# untitled.net
KiCad netlist of a schematic drawn in EAGLE
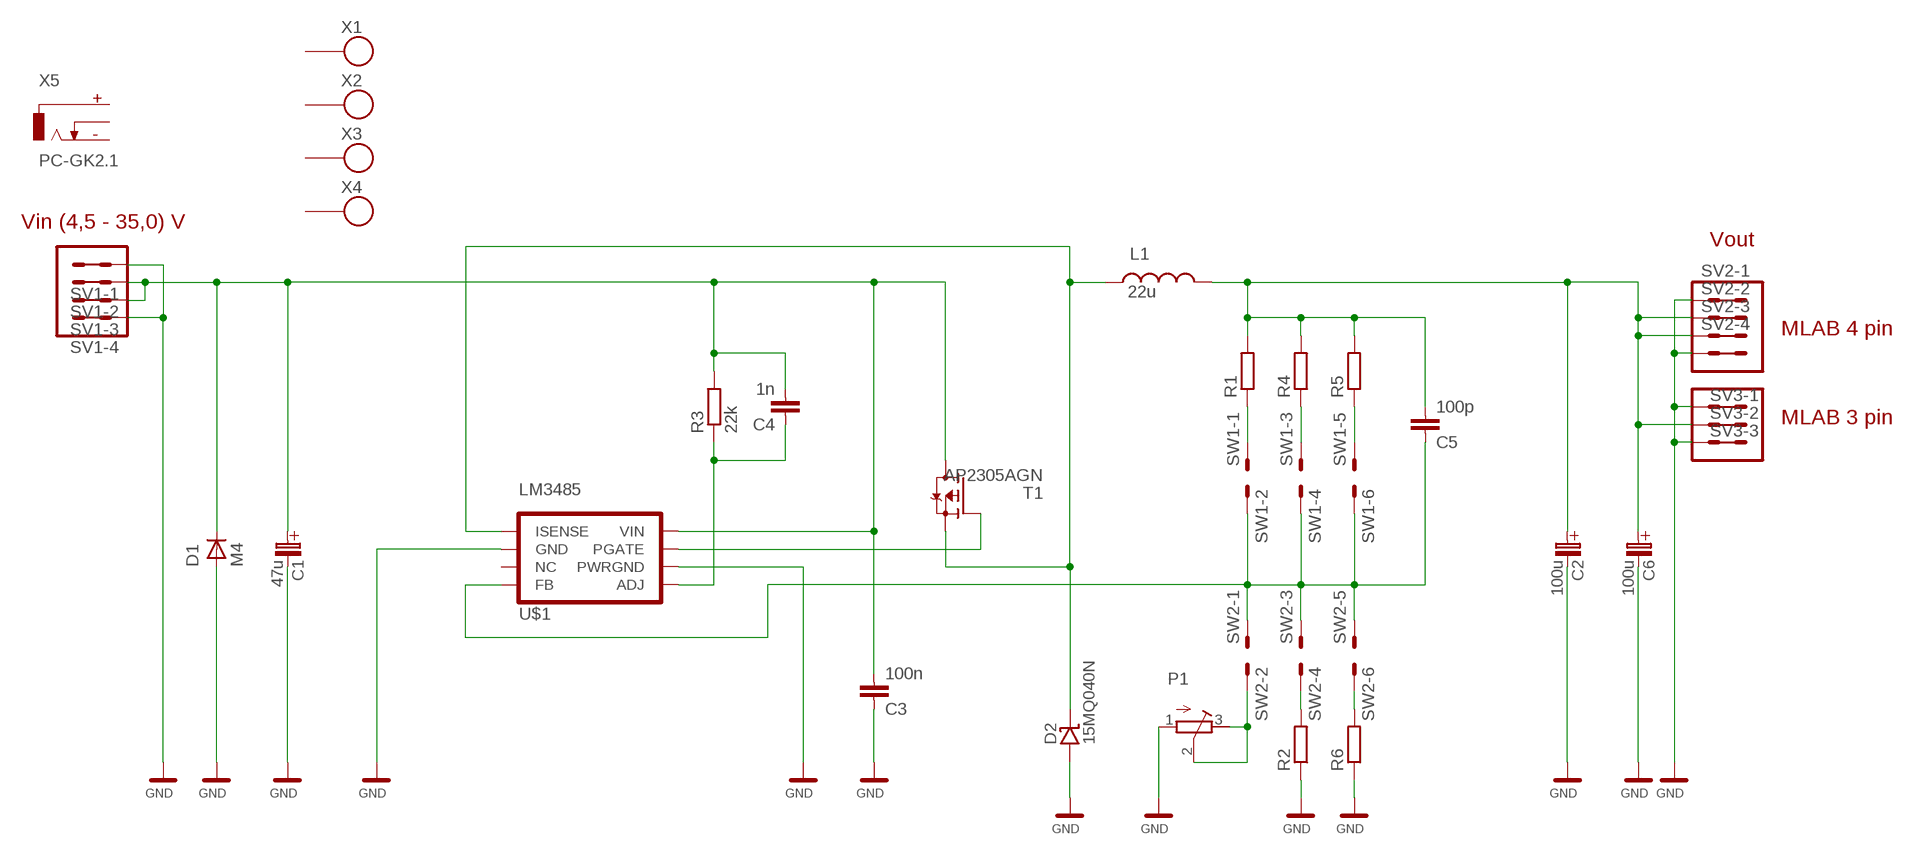
[diagram p0: schematic, sheet 1]

(export (version "E")
  (design (tool "Eeschema 10.0.6"))
  (components
    (comp (ref "C1") (value "47u") (footprint "eagle-import:C") (libsource (lib "eagle-import") (part "C")))
    (comp (ref "C2") (value "100u") (footprint "eagle-import:C") (libsource (lib "eagle-import") (part "C")))
    (comp (ref "C3")
      (value "100n")
      (footprint "eagle-import:C0805")
      (libsource (lib "eagle-import") (part "C0805"))
    )
    (comp (ref "C4")
      (value "1n")
      (footprint "eagle-import:C0805")
      (libsource (lib "eagle-import") (part "C0805"))
    )
    (comp (ref "C5")
      (value "100p")
      (footprint "eagle-import:C0805")
      (libsource (lib "eagle-import") (part "C0805"))
    )
    (comp (ref "C6") (value "100u") (footprint "eagle-import:C") (libsource (lib "eagle-import") (part "C")))
    (comp (ref "D1")
      (value "M4")
      (footprint "eagle-import:SMA")
      (libsource (lib "eagle-import") (part "D-OB.SMA"))
    )
    (comp (ref "D2")
      (value "15MQ040N")
      (footprint "eagle-import:SMA")
      (libsource (lib "eagle-import") (part "D-SHOTKY-SMA"))
    )
    (comp (ref "L1")
      (value "22u")
      (footprint "eagle-import:DE1205-10")
      (libsource (lib "eagle-import") (part "DE1205-10"))
    )
    (comp (ref "P1")
      (value "TRIMR_CA6XV")
      (footprint "eagle-import:TRIM_CA6XV")
      (libsource (lib "eagle-import") (part "TRIMR_CA6XV"))
    )
    (comp (ref "R1")
      (value "R0805")
      (footprint "eagle-import:0805")
      (libsource (lib "eagle-import") (part "R0805"))
    )
    (comp (ref "R2")
      (value "R0805")
      (footprint "eagle-import:0805")
      (libsource (lib "eagle-import") (part "R0805"))
    )
    (comp (ref "R3")
      (value "22k")
      (footprint "eagle-import:0805")
      (libsource (lib "eagle-import") (part "R0805"))
    )
    (comp (ref "R4")
      (value "R0805")
      (footprint "eagle-import:0805")
      (libsource (lib "eagle-import") (part "R0805"))
    )
    (comp (ref "R5")
      (value "R0805")
      (footprint "eagle-import:0805")
      (libsource (lib "eagle-import") (part "R0805"))
    )
    (comp (ref "R6")
      (value "R0805")
      (footprint "eagle-import:0805")
      (libsource (lib "eagle-import") (part "R0805"))
    )
    (comp (ref "SV1")
      (value "MA04-2")
      (footprint "eagle-import:MA04-2")
      (libsource (lib "eagle-import") (part "MA04-2"))
    )
    (comp (ref "SV2")
      (value "MA04-2")
      (footprint "eagle-import:MA04-2")
      (libsource (lib "eagle-import") (part "MA04-2"))
    )
    (comp (ref "SV3")
      (value "MA03-2")
      (footprint "eagle-import:MA03-2")
      (libsource (lib "eagle-import") (part "MA03-2"))
    )
    (comp (ref "SW1")
      (value "MA03-3")
      (footprint "eagle-import:MA03-2")
      (libsource (lib "eagle-import") (part "MA03-3"))
    )
    (comp (ref "SW2")
      (value "MA03-3")
      (footprint "eagle-import:MA03-2")
      (libsource (lib "eagle-import") (part "MA03-3"))
    )
    (comp (ref "T1")
      (value "AP2305AGN")
      (footprint "eagle-import:SOT23")
      (libsource (lib "eagle-import") (part "AP2305AGN"))
    )
    (comp (ref "U$1")
      (value "LM3485")
      (footprint "eagle-import:MSOP-8")
      (libsource (lib "eagle-import") (part "LM3485"))
    )
    (comp (ref "X1")
      (value "SROUB3M")
      (footprint "eagle-import:SROUB3M")
      (libsource (lib "eagle-import") (part "SROUB3M"))
    )
    (comp (ref "X2")
      (value "SROUB3M")
      (footprint "eagle-import:SROUB3M")
      (libsource (lib "eagle-import") (part "SROUB3M"))
    )
    (comp (ref "X3")
      (value "SROUB3M")
      (footprint "eagle-import:SROUB3M")
      (libsource (lib "eagle-import") (part "SROUB3M"))
    )
    (comp (ref "X4")
      (value "SROUB3M")
      (footprint "eagle-import:SROUB3M")
      (libsource (lib "eagle-import") (part "SROUB3M"))
    )
    (comp (ref "X5")
      (value "DC2.1MM")
      (footprint "eagle-import:DC2.1MM")
      (libsource (lib "eagle-import") (part "DC2.1MM"))
    )
  )
  (nets
    (net (code "1") (name "GND") (class "Default")
      (node (ref "C1") (pin "-") (pinfunction "C_EL-_-") (pintype "passive"))
      (node (ref "C2") (pin "-") (pinfunction "C_EL-_-") (pintype "passive"))
      (node (ref "C3") (pin "1") (pinfunction "1_1") (pintype "passive"))
      (node (ref "C6") (pin "-") (pinfunction "C_EL-_-") (pintype "passive"))
      (node (ref "D1") (pin "A") (pinfunction "A_A") (pintype "passive"))
      (node (ref "D2") (pin "A") (pinfunction "A_A") (pintype "passive"))
      (node (ref "P1") (pin "1") (pinfunction "1_1") (pintype "passive"))
      (node (ref "R2") (pin "1") (pinfunction "1_1") (pintype "passive"))
      (node (ref "R6") (pin "1") (pinfunction "1_1") (pintype "passive"))
      (node (ref "SV1") (pin "1") (pinfunction "K_1") (pintype "passive"))
      (node (ref "SV1") (pin "2") (pinfunction "K_2") (pintype "passive"))
      (node (ref "SV1") (pin "7") (pinfunction "K_7") (pintype "passive"))
      (node (ref "SV1") (pin "8") (pinfunction "K_8") (pintype "passive"))
      (node (ref "SV2") (pin "1") (pinfunction "K_1") (pintype "passive"))
      (node (ref "SV2") (pin "2") (pinfunction "K_2") (pintype "passive"))
      (node (ref "SV2") (pin "7") (pinfunction "K_7") (pintype "passive"))
      (node (ref "SV2") (pin "8") (pinfunction "K_8") (pintype "passive"))
      (node (ref "SV3") (pin "1") (pinfunction "K_1") (pintype "passive"))
      (node (ref "SV3") (pin "2") (pinfunction "K_2") (pintype "passive"))
      (node (ref "SV3") (pin "5") (pinfunction "K_5") (pintype "passive"))
      (node (ref "SV3") (pin "6") (pinfunction "K_6") (pintype "passive"))
      (node (ref "U$1") (pin "2") (pinfunction "GND_2") (pintype "passive"))
      (node (ref "U$1") (pin "6") (pinfunction "PWRGND_6") (pintype "passive"))
    )
    (net (code "2") (name "Net-(C1-C_EL+)") (class "Default")
      (node (ref "C1") (pin "+") (pinfunction "C_EL+_+") (pintype "passive"))
      (node (ref "C3") (pin "2") (pinfunction "2_2") (pintype "passive"))
      (node (ref "C4") (pin "2") (pinfunction "2_2") (pintype "passive"))
      (node (ref "D1") (pin "K") (pinfunction "C_K") (pintype "passive"))
      (node (ref "R3") (pin "2") (pinfunction "2_2") (pintype "passive"))
      (node (ref "SV1") (pin "3") (pinfunction "K_3") (pintype "passive"))
      (node (ref "SV1") (pin "4") (pinfunction "K_4") (pintype "passive"))
      (node (ref "SV1") (pin "5") (pinfunction "K_5") (pintype "passive"))
      (node (ref "SV1") (pin "6") (pinfunction "K_6") (pintype "passive"))
      (node (ref "T1") (pin "3") (pinfunction "D_3") (pintype "passive"))
      (node (ref "U$1") (pin "8") (pinfunction "VIN_8") (pintype "passive"))
    )
    (net (code "3") (name "Net-(C2-C_EL+)") (class "Default")
      (node (ref "C2") (pin "+") (pinfunction "C_EL+_+") (pintype "passive"))
      (node (ref "C5") (pin "2") (pinfunction "2_2") (pintype "passive"))
      (node (ref "C6") (pin "+") (pinfunction "C_EL+_+") (pintype "passive"))
      (node (ref "L1") (pin "P$2") (pinfunction "2_P$2") (pintype "passive"))
      (node (ref "R1") (pin "2") (pinfunction "2_2") (pintype "passive"))
      (node (ref "R4") (pin "2") (pinfunction "2_2") (pintype "passive"))
      (node (ref "R5") (pin "2") (pinfunction "2_2") (pintype "passive"))
      (node (ref "SV2") (pin "3") (pinfunction "K_3") (pintype "passive"))
      (node (ref "SV2") (pin "4") (pinfunction "K_4") (pintype "passive"))
      (node (ref "SV2") (pin "5") (pinfunction "K_5") (pintype "passive"))
      (node (ref "SV2") (pin "6") (pinfunction "K_6") (pintype "passive"))
      (node (ref "SV3") (pin "3") (pinfunction "K_3") (pintype "passive"))
      (node (ref "SV3") (pin "4") (pinfunction "K_4") (pintype "passive"))
    )
    (net (code "4") (name "Net-(L1-1)") (class "Default")
      (node (ref "D2") (pin "K") (pinfunction "K_K") (pintype "passive"))
      (node (ref "L1") (pin "P$1") (pinfunction "1_P$1") (pintype "passive"))
      (node (ref "T1") (pin "2") (pinfunction "S_2") (pintype "passive"))
      (node (ref "U$1") (pin "1") (pinfunction "ISENSE_1") (pintype "passive"))
    )
    (net (code "5") (name "Net-(SW1A-P$1)") (class "Default")
      (node (ref "R1") (pin "1") (pinfunction "1_1") (pintype "passive"))
      (node (ref "SW1") (pin "1") (pinfunction "P$1_1") (pintype "passive"))
    )
    (net (code "6") (name "Net-(SW1B-P$1)") (class "Default")
      (node (ref "C5") (pin "1") (pinfunction "1_1") (pintype "passive"))
      (node (ref "SW1") (pin "2") (pinfunction "P$1_2") (pintype "passive"))
      (node (ref "SW1") (pin "4") (pinfunction "P$1_4") (pintype "passive"))
      (node (ref "SW1") (pin "6") (pinfunction "P$1_6") (pintype "passive"))
      (node (ref "SW2") (pin "1") (pinfunction "P$1_1") (pintype "passive"))
      (node (ref "SW2") (pin "3") (pinfunction "P$1_3") (pintype "passive"))
      (node (ref "SW2") (pin "5") (pinfunction "P$1_5") (pintype "passive"))
      (node (ref "U$1") (pin "4") (pinfunction "FB_4") (pintype "passive"))
    )
    (net (code "7") (name "Net-(SW1C-P$1)") (class "Default")
      (node (ref "R4") (pin "1") (pinfunction "1_1") (pintype "passive"))
      (node (ref "SW1") (pin "3") (pinfunction "P$1_3") (pintype "passive"))
    )
    (net (code "8") (name "Net-(SW1E-P$1)") (class "Default")
      (node (ref "R5") (pin "1") (pinfunction "1_1") (pintype "passive"))
      (node (ref "SW1") (pin "5") (pinfunction "P$1_5") (pintype "passive"))
    )
    (net (code "9") (name "Net-(SW2B-P$1)") (class "Default")
      (node (ref "P1") (pin "2") (pinfunction "2_2") (pintype "passive"))
      (node (ref "P1") (pin "3") (pinfunction "3_3") (pintype "passive"))
      (node (ref "SW2") (pin "2") (pinfunction "P$1_2") (pintype "passive"))
    )
    (net (code "10") (name "Net-(SW2D-P$1)") (class "Default")
      (node (ref "R2") (pin "2") (pinfunction "2_2") (pintype "passive"))
      (node (ref "SW2") (pin "4") (pinfunction "P$1_4") (pintype "passive"))
    )
    (net (code "11") (name "Net-(SW2F-P$1)") (class "Default")
      (node (ref "R6") (pin "2") (pinfunction "2_2") (pintype "passive"))
      (node (ref "SW2") (pin "6") (pinfunction "P$1_6") (pintype "passive"))
    )
    (net (code "12") (name "Net-(T1-G)") (class "Default")
      (node (ref "T1") (pin "1") (pinfunction "G_1") (pintype "passive"))
      (node (ref "U$1") (pin "7") (pinfunction "PGATE_7") (pintype "passive"))
    )
    (net (code "13") (name "Net-(U$1-ADJ)") (class "Default")
      (node (ref "C4") (pin "1") (pinfunction "1_1") (pintype "passive"))
      (node (ref "R3") (pin "1") (pinfunction "1_1") (pintype "passive"))
      (node (ref "U$1") (pin "5") (pinfunction "ADJ_5") (pintype "passive"))
    )
    (net (code "14") (name "unconnected-(U$1-NC-Pad3)") (class "Default")
      (node (ref "U$1") (pin "3") (pinfunction "NC_3") (pintype "passive"))
    )
    (net (code "15") (name "unconnected-(X1-PadP$1)") (class "Default")
      (node (ref "X1") (pin "P$1") (pinfunction "P$1_P$1") (pintype "bidirectional"))
    )
    (net (code "16") (name "unconnected-(X2-PadP$1)") (class "Default")
      (node (ref "X2") (pin "P$1") (pinfunction "P$1_P$1") (pintype "bidirectional"))
    )
    (net (code "17") (name "unconnected-(X3-PadP$1)") (class "Default")
      (node (ref "X3") (pin "P$1") (pinfunction "P$1_P$1") (pintype "bidirectional"))
    )
    (net (code "18") (name "unconnected-(X4-PadP$1)") (class "Default")
      (node (ref "X4") (pin "P$1") (pinfunction "P$1_P$1") (pintype "bidirectional"))
    )
    (net (code "19") (name "unconnected-(X5---PadGND)") (class "Default")
      (node (ref "X5") (pin "GND") (pinfunction "-_GND") (pintype "passive"))
    )
    (net (code "20") (name "unconnected-(X5-Pad+)") (class "Default")
      (node (ref "X5") (pin "+") (pinfunction "+_+") (pintype "passive"))
    )
    (net (code "21") (name "unconnected-(X5-PadSW)") (class "Default")
      (node (ref "X5") (pin "SW") (pinfunction "SW_SW") (pintype "passive"))
    )
  )
)
